# utrak-v2.net
KiCad netlist of a schematic drawn in EAGLE
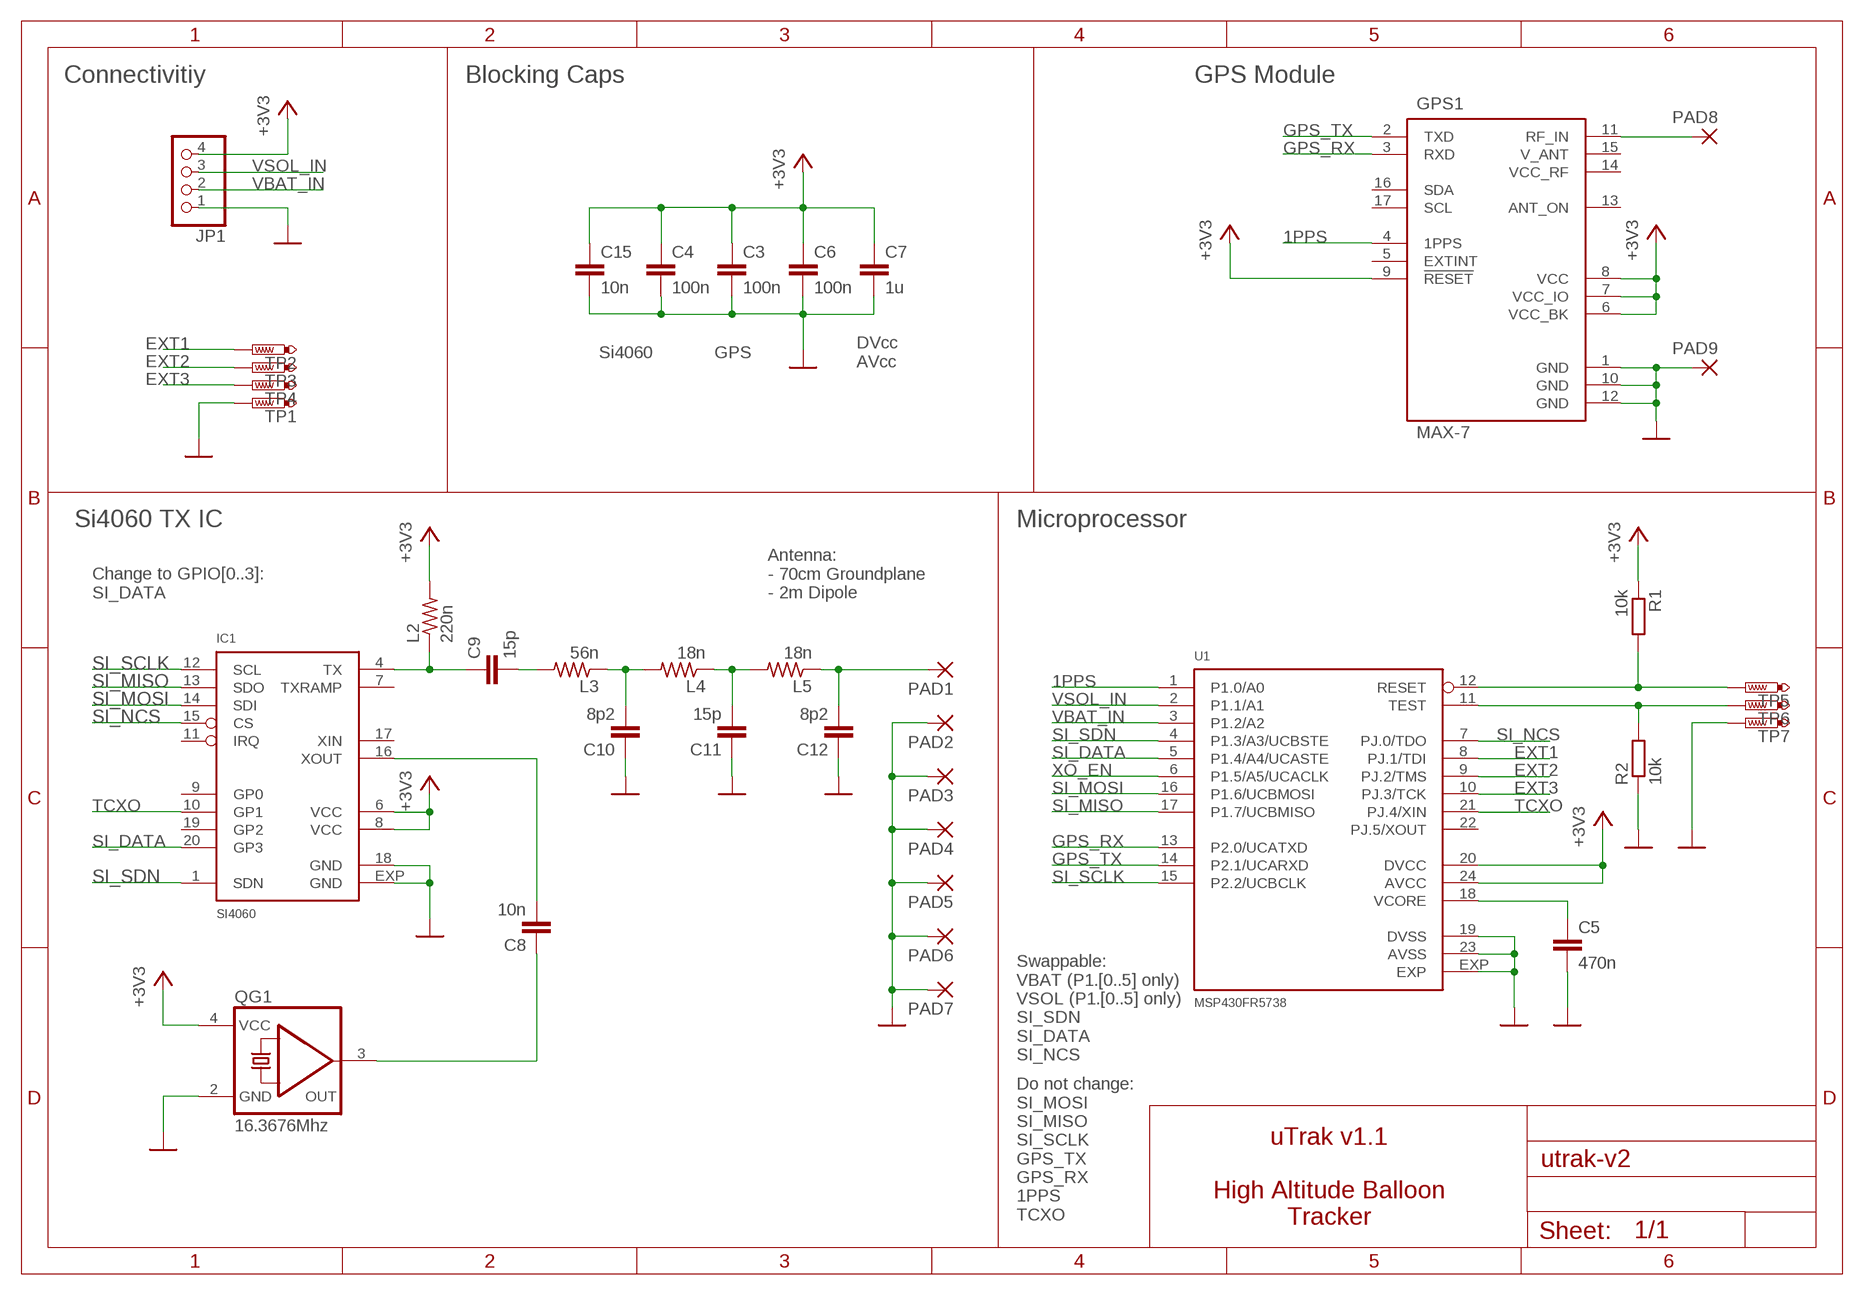
[diagram p0: schematic, sheet 1]

(export (version "E")
  (design (tool "Eeschema 10.0.6"))
  (components
    (comp (ref "C3")
      (value "100n")
      (footprint "eagle-import:C0402")
      (fields (field (name "PARTNO") "81-GRM155R71C104KA88"))
      (libsource (lib "eagle-import") (part "C-EUC0402"))
    )
    (comp (ref "C4")
      (value "100n")
      (footprint "eagle-import:C0402")
      (fields (field (name "PARTNO") "81-GRM155R71C104KA88"))
      (libsource (lib "eagle-import") (part "C-EUC0402"))
    )
    (comp (ref "C5")
      (value "470n")
      (footprint "eagle-import:C0603")
      (fields (field (name "PARTNO") "81-GCM188R71C474KA5D"))
      (libsource (lib "eagle-import") (part "C-EUC0603"))
    )
    (comp (ref "C6")
      (value "100n")
      (footprint "eagle-import:C0402")
      (fields (field (name "PARTNO") "81-GRM155R71C104KA88"))
      (libsource (lib "eagle-import") (part "C-EUC0402"))
    )
    (comp (ref "C7")
      (value "1u")
      (footprint "eagle-import:C0603")
      (fields (field (name "PARTNO") "81-GRM39R105K10"))
      (libsource (lib "eagle-import") (part "C-EUC0603"))
    )
    (comp (ref "C8")
      (value "10n")
      (footprint "eagle-import:C0402")
      (fields (field (name "PARTNO") "81-GRM155R71H103MA8D"))
      (libsource (lib "eagle-import") (part "C-EUC0402"))
    )
    (comp (ref "C9")
      (value "15p")
      (footprint "eagle-import:C0402")
      (fields (field (name "PARTNO") "81-GRM1555C1H150FA1D"))
      (libsource (lib "eagle-import") (part "C-EUC0402"))
    )
    (comp (ref "C10")
      (value "8p2")
      (footprint "eagle-import:C0402")
      (fields (field (name "PARTNO") "81-GRM1555C1H8R2BA1D"))
      (libsource (lib "eagle-import") (part "C-EUC0402"))
    )
    (comp (ref "C11")
      (value "15p")
      (footprint "eagle-import:C0402")
      (fields (field (name "PARTNO") "81-GRM1555C1H150FA1D"))
      (libsource (lib "eagle-import") (part "C-EUC0402"))
    )
    (comp (ref "C12")
      (value "8p2")
      (footprint "eagle-import:C0402")
      (fields (field (name "PARTNO") "81-GRM1555C1H8R2BA1D"))
      (libsource (lib "eagle-import") (part "C-EUC0402"))
    )
    (comp (ref "C15")
      (value "10n")
      (footprint "eagle-import:C0402")
      (fields (field (name "PARTNO") "81-GRM155R71H103MA8D"))
      (libsource (lib "eagle-import") (part "C-EUC0402"))
    )
    (comp (ref "GPS1")
      (value "MAX-7")
      (footprint "eagle-import:UBLOX-7")
      (libsource (lib "eagle-import") (part "MAX-7"))
    )
    (comp (ref "IC1")
      (value "SI4060")
      (footprint "eagle-import:QFN20")
      (fields (field (name "PARTNO") "634-SI4060-B1B-FMR"))
      (libsource (lib "eagle-import") (part "SI4060"))
    )
    (comp (ref "JP1")
      (value "PINHD-1X4")
      (footprint "eagle-import:1X04")
      (libsource (lib "eagle-import") (part "PINHD-1X4"))
    )
    (comp (ref "L2")
      (value "220n")
      (footprint "eagle-import:R0603")
      (fields (field (name "PARTNO") "994-0603CS-R22XGLW"))
      (libsource (lib "eagle-import") (part "R-US_R0603"))
    )
    (comp (ref "L3")
      (value "56n")
      (footprint "eagle-import:R0603")
      (fields (field (name "PARTNO") "994-0603CS-56NXJLW"))
      (libsource (lib "eagle-import") (part "R-US_R0603"))
    )
    (comp (ref "L4")
      (value "18n")
      (footprint "eagle-import:R0603")
      (fields (field (name "PARTNO") "994-0603CS-18NXJLU"))
      (libsource (lib "eagle-import") (part "R-US_R0603"))
    )
    (comp (ref "L5")
      (value "18n")
      (footprint "eagle-import:R0603")
      (fields (field (name "PARTNO") "994-0603CS-18NXJLU"))
      (libsource (lib "eagle-import") (part "R-US_R0603"))
    )
    (comp (ref "PAD1")
      (value "SMD2")
      (footprint "eagle-import:SMD1,27-2,54")
      (libsource (lib "eagle-import") (part "SMD2"))
    )
    (comp (ref "PAD2")
      (value "SMD2")
      (footprint "eagle-import:SMD1,27-2,54")
      (libsource (lib "eagle-import") (part "SMD2"))
    )
    (comp (ref "PAD3")
      (value "SMD2")
      (footprint "eagle-import:SMD1,27-2,54")
      (libsource (lib "eagle-import") (part "SMD2"))
    )
    (comp (ref "PAD4")
      (value "SMD2")
      (footprint "eagle-import:SMD1,27-2,54")
      (libsource (lib "eagle-import") (part "SMD2"))
    )
    (comp (ref "PAD5")
      (value "SMD2")
      (footprint "eagle-import:SMD1,27-2,54")
      (libsource (lib "eagle-import") (part "SMD2"))
    )
    (comp (ref "PAD6")
      (value "SMD2")
      (footprint "eagle-import:SMD1,27-2,54")
      (libsource (lib "eagle-import") (part "SMD2"))
    )
    (comp (ref "PAD7")
      (value "SMD2")
      (footprint "eagle-import:SMD1,27-2,54")
      (libsource (lib "eagle-import") (part "SMD2"))
    )
    (comp (ref "PAD8")
      (value "SMD2")
      (footprint "eagle-import:SMD1,27-2,54")
      (libsource (lib "eagle-import") (part "SMD2"))
    )
    (comp (ref "PAD9")
      (value "SMD2")
      (footprint "eagle-import:SMD1,27-2,54")
      (libsource (lib "eagle-import") (part "SMD2"))
    )
    (comp (ref "QG1")
      (value "16.3676Mhz")
      (footprint "eagle-import:CTS406")
      (libsource (lib "eagle-import") (part "XO"))
    )
    (comp (ref "R1")
      (value "10k")
      (footprint "eagle-import:R0402")
      (fields (field (name "PARTNO") "603-RC0402FR-0710KL"))
      (libsource (lib "eagle-import") (part "R-EU_R0402"))
    )
    (comp (ref "R2")
      (value "10k")
      (footprint "eagle-import:R0402")
      (fields (field (name "PARTNO") "603-RC0402FR-0710KL"))
      (libsource (lib "eagle-import") (part "R-EU_R0402"))
    )
    (comp (ref "TP1")
      (value "PTR1TP10SQ")
      (footprint "eagle-import:TP10SQ")
      (libsource (lib "eagle-import") (part "PTR1TP10SQ"))
    )
    (comp (ref "TP2")
      (value "PTR1TP10SQ")
      (footprint "eagle-import:TP10SQ")
      (libsource (lib "eagle-import") (part "PTR1TP10SQ"))
    )
    (comp (ref "TP3")
      (value "PTR1TP10SQ")
      (footprint "eagle-import:TP10SQ")
      (libsource (lib "eagle-import") (part "PTR1TP10SQ"))
    )
    (comp (ref "TP4")
      (value "PTR1TP10SQ")
      (footprint "eagle-import:TP10SQ")
      (libsource (lib "eagle-import") (part "PTR1TP10SQ"))
    )
    (comp (ref "TP5")
      (value "PTR1TP10SQ")
      (footprint "eagle-import:TP10SQ")
      (libsource (lib "eagle-import") (part "PTR1TP10SQ"))
    )
    (comp (ref "TP6")
      (value "PTR1TP10SQ")
      (footprint "eagle-import:TP10SQ")
      (libsource (lib "eagle-import") (part "PTR1TP10SQ"))
    )
    (comp (ref "TP7")
      (value "PTR1TP10SQ")
      (footprint "eagle-import:TP10SQ")
      (libsource (lib "eagle-import") (part "PTR1TP10SQ"))
    )
    (comp (ref "U1")
      (value "MSP430FR5738")
      (footprint "eagle-import:QFN24-4X4")
      (fields (field (name "PARTNO") "595-SP430FR5738IRGER"))
      (libsource (lib "eagle-import") (part "MSP430FR5738"))
    )
  )
  (nets
    (net (code "1") (name "+3V3") (class "Default")
      (node (ref "C15") (pin "1") (pinfunction "1_1") (pintype "passive"))
      (node (ref "C3") (pin "1") (pinfunction "1_1") (pintype "passive"))
      (node (ref "C4") (pin "1") (pinfunction "1_1") (pintype "passive"))
      (node (ref "C6") (pin "1") (pinfunction "1_1") (pintype "passive"))
      (node (ref "C7") (pin "1") (pinfunction "1_1") (pintype "passive"))
      (node (ref "GPS1") (pin "6") (pinfunction "VCC_BK_6") (pintype "power_in"))
      (node (ref "GPS1") (pin "7") (pinfunction "VCC_IO_7") (pintype "power_in"))
      (node (ref "GPS1") (pin "8") (pinfunction "VCC_8") (pintype "power_in"))
      (node (ref "GPS1") (pin "9") (pinfunction "~{RESET}_9") (pintype "bidirectional"))
      (node (ref "IC1") (pin "6") (pinfunction "VCC_6") (pintype "power_in"))
      (node (ref "IC1") (pin "8") (pinfunction "VCC_8") (pintype "power_in"))
      (node (ref "JP1") (pin "4") (pinfunction "4_4") (pintype "passive"))
      (node (ref "L2") (pin "2") (pinfunction "2_2") (pintype "passive"))
      (node (ref "QG1") (pin "4") (pinfunction "VCC_4") (pintype "power_in"))
      (node (ref "R1") (pin "1") (pinfunction "1_1") (pintype "passive"))
      (node (ref "U1") (pin "20") (pinfunction "DVCC_20") (pintype "power_in"))
      (node (ref "U1") (pin "24") (pinfunction "AVCC_24") (pintype "power_in"))
    )
    (net (code "2") (name "/1PPS") (class "Default")
      (node (ref "GPS1") (pin "4") (pinfunction "1PPS_4") (pintype "bidirectional"))
      (node (ref "U1") (pin "1") (pinfunction "P1.0/A0_1") (pintype "bidirectional"))
    )
    (net (code "3") (name "/EXT1") (class "Default")
      (node (ref "TP2") (pin "TP") (pinfunction "TP_TP") (pintype "input"))
      (node (ref "U1") (pin "8") (pinfunction "PJ.1/TDI_8") (pintype "bidirectional"))
    )
    (net (code "4") (name "/EXT2") (class "Default")
      (node (ref "TP3") (pin "TP") (pinfunction "TP_TP") (pintype "input"))
      (node (ref "U1") (pin "9") (pinfunction "PJ.2/TMS_9") (pintype "bidirectional"))
    )
    (net (code "5") (name "/EXT3") (class "Default")
      (node (ref "TP4") (pin "TP") (pinfunction "TP_TP") (pintype "input"))
      (node (ref "U1") (pin "10") (pinfunction "PJ.3/TCK_10") (pintype "bidirectional"))
    )
    (net (code "6") (name "/GPS_RX") (class "Default")
      (node (ref "GPS1") (pin "3") (pinfunction "RXD_3") (pintype "bidirectional"))
      (node (ref "U1") (pin "13") (pinfunction "P2.0/UCATXD_13") (pintype "bidirectional"))
    )
    (net (code "7") (name "/GPS_TX") (class "Default")
      (node (ref "GPS1") (pin "2") (pinfunction "TXD_2") (pintype "bidirectional"))
      (node (ref "U1") (pin "14") (pinfunction "P2.1/UCARXD_14") (pintype "bidirectional"))
    )
    (net (code "8") (name "/SI_DATA") (class "Default")
      (node (ref "IC1") (pin "20") (pinfunction "GP3_20") (pintype "bidirectional"))
      (node (ref "U1") (pin "5") (pinfunction "P1.4/A4/UCASTE_5") (pintype "bidirectional"))
    )
    (net (code "9") (name "/SI_MISO") (class "Default")
      (node (ref "IC1") (pin "13") (pinfunction "SDO_13") (pintype "bidirectional"))
      (node (ref "U1") (pin "17") (pinfunction "P1.7/UCBMISO_17") (pintype "bidirectional"))
    )
    (net (code "10") (name "/SI_MOSI") (class "Default")
      (node (ref "IC1") (pin "14") (pinfunction "SDI_14") (pintype "bidirectional"))
      (node (ref "U1") (pin "16") (pinfunction "P1.6/UCBMOSI_16") (pintype "bidirectional"))
    )
    (net (code "11") (name "/SI_NCS") (class "Default")
      (node (ref "IC1") (pin "15") (pinfunction "CS_15") (pintype "bidirectional"))
      (node (ref "U1") (pin "7") (pinfunction "PJ.0/TDO_7") (pintype "bidirectional"))
    )
    (net (code "12") (name "/SI_SCLK") (class "Default")
      (node (ref "IC1") (pin "12") (pinfunction "SCL_12") (pintype "bidirectional"))
      (node (ref "U1") (pin "15") (pinfunction "P2.2/UCBCLK_15") (pintype "bidirectional"))
    )
    (net (code "13") (name "/SI_SDN") (class "Default")
      (node (ref "IC1") (pin "1") (pinfunction "SDN_1") (pintype "bidirectional"))
      (node (ref "U1") (pin "4") (pinfunction "P1.3/A3/UCBSTE_4") (pintype "bidirectional"))
    )
    (net (code "14") (name "/TCXO") (class "Default")
      (node (ref "IC1") (pin "10") (pinfunction "GP1_10") (pintype "bidirectional"))
      (node (ref "U1") (pin "21") (pinfunction "PJ.4/XIN_21") (pintype "bidirectional"))
    )
    (net (code "15") (name "/VBAT_IN") (class "Default")
      (node (ref "JP1") (pin "2") (pinfunction "2_2") (pintype "passive"))
      (node (ref "U1") (pin "3") (pinfunction "P1.2/A2_3") (pintype "bidirectional"))
    )
    (net (code "16") (name "/VSOL_IN") (class "Default")
      (node (ref "JP1") (pin "3") (pinfunction "3_3") (pintype "passive"))
      (node (ref "U1") (pin "2") (pinfunction "P1.1/A1_2") (pintype "bidirectional"))
    )
    (net (code "17") (name "/XO_EN") (class "Default")
      (node (ref "U1") (pin "6") (pinfunction "P1.5/A5/UCACLK_6") (pintype "bidirectional"))
    )
    (net (code "18") (name "GND") (class "Default")
      (node (ref "C10") (pin "1") (pinfunction "1_1") (pintype "passive"))
      (node (ref "C11") (pin "1") (pinfunction "1_1") (pintype "passive"))
      (node (ref "C12") (pin "1") (pinfunction "1_1") (pintype "passive"))
      (node (ref "C15") (pin "2") (pinfunction "2_2") (pintype "passive"))
      (node (ref "C3") (pin "2") (pinfunction "2_2") (pintype "passive"))
      (node (ref "C4") (pin "2") (pinfunction "2_2") (pintype "passive"))
      (node (ref "C5") (pin "2") (pinfunction "2_2") (pintype "passive"))
      (node (ref "C6") (pin "2") (pinfunction "2_2") (pintype "passive"))
      (node (ref "C7") (pin "2") (pinfunction "2_2") (pintype "passive"))
      (node (ref "GPS1") (pin "1") (pinfunction "GND_1") (pintype "power_in"))
      (node (ref "GPS1") (pin "10") (pinfunction "GND_10") (pintype "power_in"))
      (node (ref "GPS1") (pin "12") (pinfunction "GND_12") (pintype "power_in"))
      (node (ref "IC1") (pin "18") (pinfunction "GND_18") (pintype "power_in"))
      (node (ref "IC1") (pin "EXP") (pinfunction "GND_EXP") (pintype "power_in"))
      (node (ref "JP1") (pin "1") (pinfunction "1_1") (pintype "passive"))
      (node (ref "PAD2") (pin "1") (pinfunction "P_1") (pintype "passive"))
      (node (ref "PAD3") (pin "1") (pinfunction "P_1") (pintype "passive"))
      (node (ref "PAD4") (pin "1") (pinfunction "P_1") (pintype "passive"))
      (node (ref "PAD5") (pin "1") (pinfunction "P_1") (pintype "passive"))
      (node (ref "PAD6") (pin "1") (pinfunction "P_1") (pintype "passive"))
      (node (ref "PAD7") (pin "1") (pinfunction "P_1") (pintype "passive"))
      (node (ref "PAD9") (pin "1") (pinfunction "P_1") (pintype "passive"))
      (node (ref "QG1") (pin "2") (pinfunction "GND_2") (pintype "power_in"))
      (node (ref "R2") (pin "1") (pinfunction "1_1") (pintype "passive"))
      (node (ref "TP1") (pin "TP") (pinfunction "TP_TP") (pintype "input"))
      (node (ref "TP7") (pin "TP") (pinfunction "TP_TP") (pintype "input"))
      (node (ref "U1") (pin "19") (pinfunction "DVSS_19") (pintype "power_in"))
      (node (ref "U1") (pin "23") (pinfunction "AVSS_23") (pintype "power_in"))
      (node (ref "U1") (pin "EXP") (pinfunction "EXP_EXP") (pintype "power_in"))
    )
    (net (code "19") (name "Net-(C9-Pad2)") (class "Default")
      (node (ref "C9") (pin "2") (pinfunction "2_2") (pintype "passive"))
      (node (ref "L3") (pin "2") (pinfunction "2_2") (pintype "passive"))
    )
    (net (code "20") (name "Net-(C10-Pad2)") (class "Default")
      (node (ref "C10") (pin "2") (pinfunction "2_2") (pintype "passive"))
      (node (ref "L3") (pin "1") (pinfunction "1_1") (pintype "passive"))
      (node (ref "L4") (pin "2") (pinfunction "2_2") (pintype "passive"))
    )
    (net (code "21") (name "Net-(C11-Pad2)") (class "Default")
      (node (ref "C11") (pin "2") (pinfunction "2_2") (pintype "passive"))
      (node (ref "L4") (pin "1") (pinfunction "1_1") (pintype "passive"))
      (node (ref "L5") (pin "2") (pinfunction "2_2") (pintype "passive"))
    )
    (net (code "22") (name "Net-(GPS1-RF_IN)") (class "Default")
      (node (ref "GPS1") (pin "11") (pinfunction "RF_IN_11") (pintype "bidirectional"))
      (node (ref "PAD8") (pin "1") (pinfunction "P_1") (pintype "passive"))
    )
    (net (code "23") (name "Net-(IC1-TX)") (class "Default")
      (node (ref "C9") (pin "1") (pinfunction "1_1") (pintype "passive"))
      (node (ref "IC1") (pin "4") (pinfunction "TX_4") (pintype "bidirectional"))
      (node (ref "L2") (pin "1") (pinfunction "1_1") (pintype "passive"))
    )
    (net (code "24") (name "Net-(IC1-XOUT)") (class "Default")
      (node (ref "C8") (pin "2") (pinfunction "2_2") (pintype "passive"))
      (node (ref "IC1") (pin "16") (pinfunction "XOUT_16") (pintype "bidirectional"))
    )
    (net (code "25") (name "Net-(PAD1-P)") (class "Default")
      (node (ref "C12") (pin "2") (pinfunction "2_2") (pintype "passive"))
      (node (ref "L5") (pin "1") (pinfunction "1_1") (pintype "passive"))
      (node (ref "PAD1") (pin "1") (pinfunction "P_1") (pintype "passive"))
    )
    (net (code "26") (name "Net-(QG1-OUT)") (class "Default")
      (node (ref "C8") (pin "1") (pinfunction "1_1") (pintype "passive"))
      (node (ref "QG1") (pin "3") (pinfunction "OUT_3") (pintype "output"))
    )
    (net (code "27") (name "Net-(U1-RESET)") (class "Default")
      (node (ref "R1") (pin "2") (pinfunction "2_2") (pintype "passive"))
      (node (ref "TP5") (pin "TP") (pinfunction "TP_TP") (pintype "input"))
      (node (ref "U1") (pin "12") (pinfunction "RESET_12") (pintype "bidirectional"))
    )
    (net (code "28") (name "Net-(U1-TEST)") (class "Default")
      (node (ref "R2") (pin "2") (pinfunction "2_2") (pintype "passive"))
      (node (ref "TP6") (pin "TP") (pinfunction "TP_TP") (pintype "input"))
      (node (ref "U1") (pin "11") (pinfunction "TEST_11") (pintype "bidirectional"))
    )
    (net (code "29") (name "Net-(U1-VCORE)") (class "Default")
      (node (ref "C5") (pin "1") (pinfunction "1_1") (pintype "passive"))
      (node (ref "U1") (pin "18") (pinfunction "VCORE_18") (pintype "power_in"))
    )
    (net (code "30") (name "unconnected-(GPS1-ANT_ON-Pad13)") (class "Default")
      (node (ref "GPS1") (pin "13") (pinfunction "ANT_ON_13") (pintype "bidirectional"))
    )
    (net (code "31") (name "unconnected-(GPS1-EXTINT-Pad5)") (class "Default")
      (node (ref "GPS1") (pin "5") (pinfunction "EXTINT_5") (pintype "bidirectional"))
    )
    (net (code "32") (name "unconnected-(GPS1-SCL-Pad17)") (class "Default")
      (node (ref "GPS1") (pin "17") (pinfunction "SCL_17") (pintype "bidirectional"))
    )
    (net (code "33") (name "unconnected-(GPS1-SDA-Pad16)") (class "Default")
      (node (ref "GPS1") (pin "16") (pinfunction "SDA_16") (pintype "bidirectional"))
    )
    (net (code "34") (name "unconnected-(GPS1-VCC_RF-Pad14)") (class "Default")
      (node (ref "GPS1") (pin "14") (pinfunction "VCC_RF_14") (pintype "bidirectional"))
    )
    (net (code "35") (name "unconnected-(GPS1-V_ANT-Pad15)") (class "Default")
      (node (ref "GPS1") (pin "15") (pinfunction "V_ANT_15") (pintype "bidirectional"))
    )
    (net (code "36") (name "unconnected-(IC1-GP0-Pad9)") (class "Default")
      (node (ref "IC1") (pin "9") (pinfunction "GP0_9") (pintype "bidirectional"))
    )
    (net (code "37") (name "unconnected-(IC1-GP2-Pad19)") (class "Default")
      (node (ref "IC1") (pin "19") (pinfunction "GP2_19") (pintype "bidirectional"))
    )
    (net (code "38") (name "unconnected-(IC1-IRQ-Pad11)") (class "Default")
      (node (ref "IC1") (pin "11") (pinfunction "IRQ_11") (pintype "bidirectional"))
    )
    (net (code "39") (name "unconnected-(IC1-TXRAMP-Pad7)") (class "Default")
      (node (ref "IC1") (pin "7") (pinfunction "TXRAMP_7") (pintype "bidirectional"))
    )
    (net (code "40") (name "unconnected-(IC1-XIN-Pad17)") (class "Default")
      (node (ref "IC1") (pin "17") (pinfunction "XIN_17") (pintype "bidirectional"))
    )
    (net (code "41") (name "unconnected-(U1-PJ.5{slash}XOUT-Pad22)") (class "Default")
      (node (ref "U1") (pin "22") (pinfunction "PJ.5/XOUT_22") (pintype "bidirectional"))
    )
  )
)
